# LCD_BT.net
KiCad netlist of a schematic drawn in Altium Designer
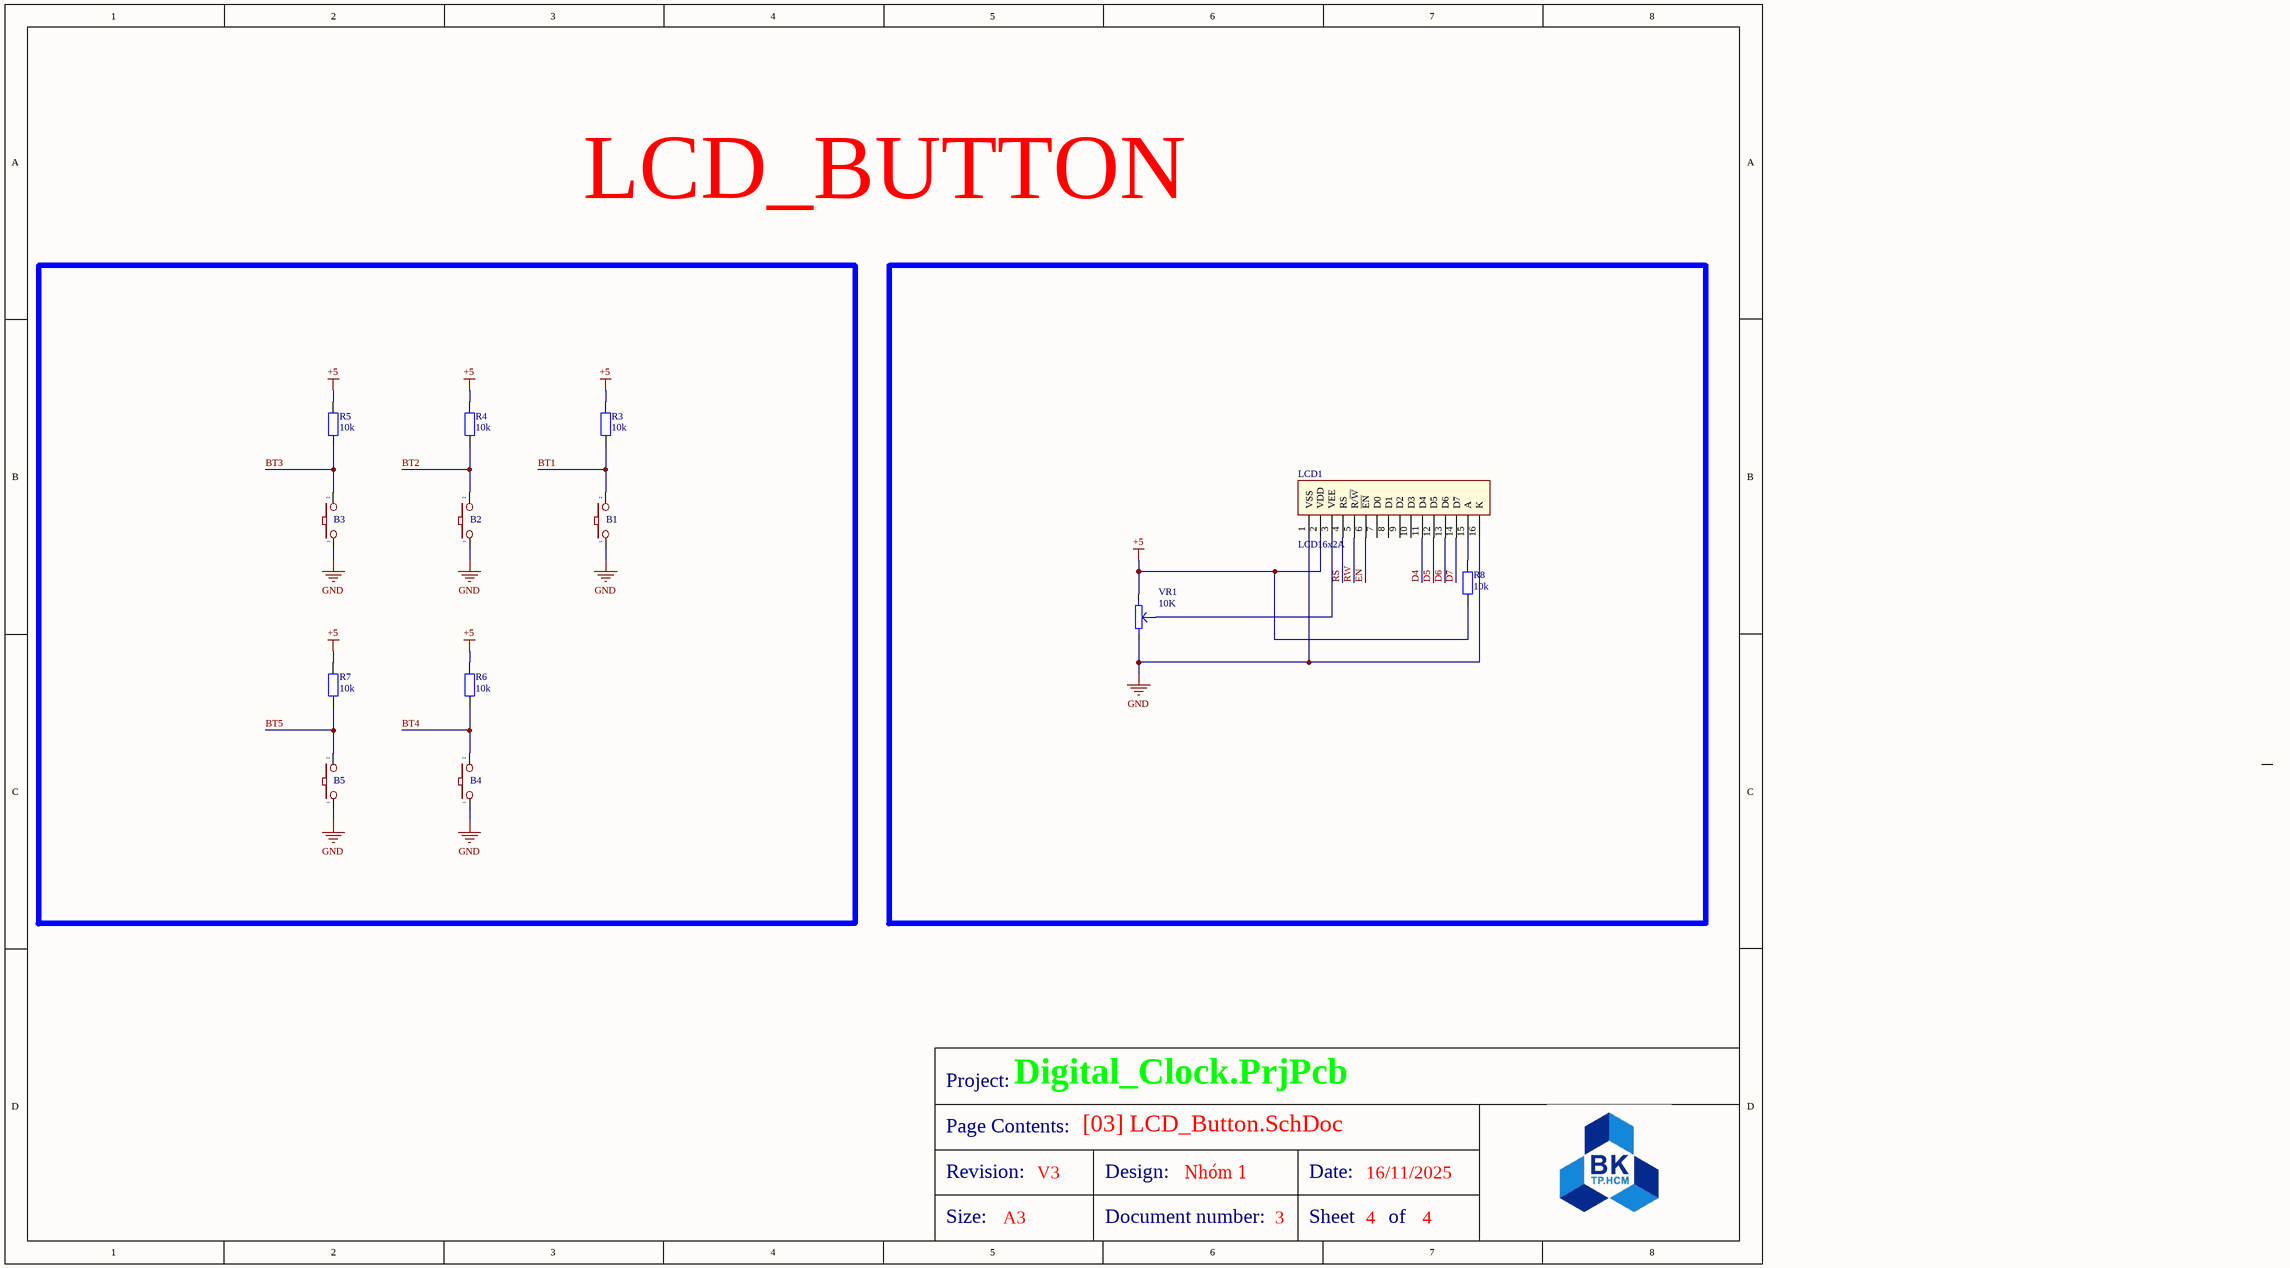
[diagram p0: LCD_BT.SchDoc]

(export (version "E")
  (design (tool "Eeschema 10.0.6"))
  (components
    (comp (ref "B1")
      (value "~")
      (footprint "SW2")
      (description "Switch button 2 pin")
      (libsource (lib "syhaunguyen") (part "SW2"))
    )
    (comp (ref "B2")
      (value "~")
      (footprint "SW2")
      (description "Switch button 2 pin")
      (libsource (lib "syhaunguyen") (part "SW2"))
    )
    (comp (ref "B3")
      (value "~")
      (footprint "SW2")
      (description "Switch button 2 pin")
      (libsource (lib "syhaunguyen") (part "SW2"))
    )
    (comp (ref "B4")
      (value "~")
      (footprint "SW2")
      (description "Switch button 2 pin")
      (libsource (lib "syhaunguyen") (part "SW2"))
    )
    (comp (ref "B5")
      (value "~")
      (footprint "SW2")
      (description "Switch button 2 pin")
      (libsource (lib "syhaunguyen") (part "SW2"))
    )
    (comp (ref "LCD1")
      (value "LCD16x2A")
      (footprint "LCD16X2")
      (description "LCD dipslay 16 char, 2 line")
      (libsource (lib "syhaunguyen") (part "LCD16x2"))
    )
    (comp (ref "R3")
      (value "10k")
      (footprint "tro smd 0603")
      (description "Căm")
      (libsource (lib "") (part "Tro Vach 1/4W 5% 10k_1"))
    )
    (comp (ref "R4")
      (value "10k")
      (footprint "tro smd 0603")
      (description "Căm")
      (libsource (lib "") (part "Tro Vach 1/4W 5% 10k_1"))
    )
    (comp (ref "R5")
      (value "10k")
      (footprint "tro smd 0603")
      (description "Căm")
      (libsource (lib "") (part "Tro Vach 1/4W 5% 10k_1"))
    )
    (comp (ref "R6")
      (value "10k")
      (footprint "tro smd 0603")
      (description "Căm")
      (libsource (lib "") (part "Tro Vach 1/4W 5% 10k_1"))
    )
    (comp (ref "R7")
      (value "10k")
      (footprint "tro smd 0603")
      (description "Căm")
      (libsource (lib "") (part "Tro Vach 1/4W 5% 10k_1"))
    )
    (comp (ref "R8")
      (value "10k")
      (footprint "tro smd 0603")
      (description "Căm")
      (libsource (lib "Resistor") (part "Tro Vach 1/4W 5% 10k"))
    )
    (comp (ref "VR1")
      (value "10K")
      (footprint "Bien Tro Tam Giac Dung")
      (description "Cắm")
      (libsource (lib "Resistor") (part "Bien tro tam giac 10K Dung"))
    )
  )
  (nets
    (net (code "1") (name "+5") (class "Default")
      (node (ref "LCD1") (pin "2") (pinfunction "VDD_2") (pintype "passive"))
      (node (ref "R3") (pin "1") (pinfunction "1_1") (pintype "passive"))
      (node (ref "R4") (pin "1") (pinfunction "1_1") (pintype "passive"))
      (node (ref "R5") (pin "1") (pinfunction "1_1") (pintype "passive"))
      (node (ref "R6") (pin "1") (pinfunction "1_1") (pintype "passive"))
      (node (ref "R7") (pin "1") (pinfunction "1_1") (pintype "passive"))
      (node (ref "R8") (pin "1") (pinfunction "1_1") (pintype "passive"))
      (node (ref "VR1") (pin "1") (pinfunction "1_1") (pintype "passive"))
    )
    (net (code "2") (name "/BT1") (class "Default")
      (node (ref "B1") (pin "2") (pinfunction "2_2") (pintype "passive"))
      (node (ref "R3") (pin "2") (pinfunction "2_2") (pintype "passive"))
    )
    (net (code "3") (name "/BT2") (class "Default")
      (node (ref "B2") (pin "2") (pinfunction "2_2") (pintype "passive"))
      (node (ref "R4") (pin "2") (pinfunction "2_2") (pintype "passive"))
    )
    (net (code "4") (name "/BT3") (class "Default")
      (node (ref "B3") (pin "2") (pinfunction "2_2") (pintype "passive"))
      (node (ref "R5") (pin "2") (pinfunction "2_2") (pintype "passive"))
    )
    (net (code "5") (name "/BT4") (class "Default")
      (node (ref "B4") (pin "2") (pinfunction "2_2") (pintype "passive"))
      (node (ref "R6") (pin "2") (pinfunction "2_2") (pintype "passive"))
    )
    (net (code "6") (name "/BT5") (class "Default")
      (node (ref "B5") (pin "2") (pinfunction "2_2") (pintype "passive"))
      (node (ref "R7") (pin "2") (pinfunction "2_2") (pintype "passive"))
    )
    (net (code "7") (name "/D4") (class "Default")
      (node (ref "LCD1") (pin "11") (pinfunction "D4_11") (pintype "passive"))
    )
    (net (code "8") (name "/D5") (class "Default")
      (node (ref "LCD1") (pin "12") (pinfunction "D5_12") (pintype "passive"))
    )
    (net (code "9") (name "/D6") (class "Default")
      (node (ref "LCD1") (pin "13") (pinfunction "D6_13") (pintype "passive"))
    )
    (net (code "10") (name "/D7") (class "Default")
      (node (ref "LCD1") (pin "14") (pinfunction "D7_14") (pintype "passive"))
    )
    (net (code "11") (name "/EN") (class "Default")
      (node (ref "LCD1") (pin "6") (pinfunction "~{EN}_6") (pintype "passive"))
    )
    (net (code "12") (name "/RS") (class "Default")
      (node (ref "LCD1") (pin "4") (pinfunction "RS_4") (pintype "passive"))
    )
    (net (code "13") (name "/RW") (class "Default")
      (node (ref "LCD1") (pin "5") (pinfunction "R/~{W}_5") (pintype "passive"))
    )
    (net (code "14") (name "GND") (class "Default")
      (node (ref "B1") (pin "1") (pinfunction "1_1") (pintype "passive"))
      (node (ref "B2") (pin "1") (pinfunction "1_1") (pintype "passive"))
      (node (ref "B3") (pin "1") (pinfunction "1_1") (pintype "passive"))
      (node (ref "B4") (pin "1") (pinfunction "1_1") (pintype "passive"))
      (node (ref "B5") (pin "1") (pinfunction "1_1") (pintype "passive"))
      (node (ref "LCD1") (pin "1") (pinfunction "VSS_1") (pintype "passive"))
      (node (ref "LCD1") (pin "16") (pinfunction "K_16") (pintype "passive"))
      (node (ref "VR1") (pin "3") (pinfunction "3_3") (pintype "passive"))
    )
    (net (code "15") (name "Net-(LCD1-A)") (class "Default")
      (node (ref "LCD1") (pin "15") (pinfunction "A_15") (pintype "passive"))
      (node (ref "R8") (pin "2") (pinfunction "2_2") (pintype "passive"))
    )
    (net (code "16") (name "Net-(LCD1-VEE)") (class "Default")
      (node (ref "LCD1") (pin "3") (pinfunction "VEE_3") (pintype "passive"))
      (node (ref "VR1") (pin "2") (pinfunction "2_2") (pintype "passive"))
    )
    (net (code "17") (name "unconnected-(LCD1-D0-Pad7)") (class "Default")
      (node (ref "LCD1") (pin "7") (pinfunction "D0_7") (pintype "passive"))
    )
    (net (code "18") (name "unconnected-(LCD1-D1-Pad8)") (class "Default")
      (node (ref "LCD1") (pin "8") (pinfunction "D1_8") (pintype "passive"))
    )
    (net (code "19") (name "unconnected-(LCD1-D2-Pad9)") (class "Default")
      (node (ref "LCD1") (pin "9") (pinfunction "D2_9") (pintype "passive"))
    )
    (net (code "20") (name "unconnected-(LCD1-D3-Pad10)") (class "Default")
      (node (ref "LCD1") (pin "10") (pinfunction "D3_10") (pintype "passive"))
    )
  )
)
